# SS4.net
KiCad netlist of a schematic drawn in EAGLE
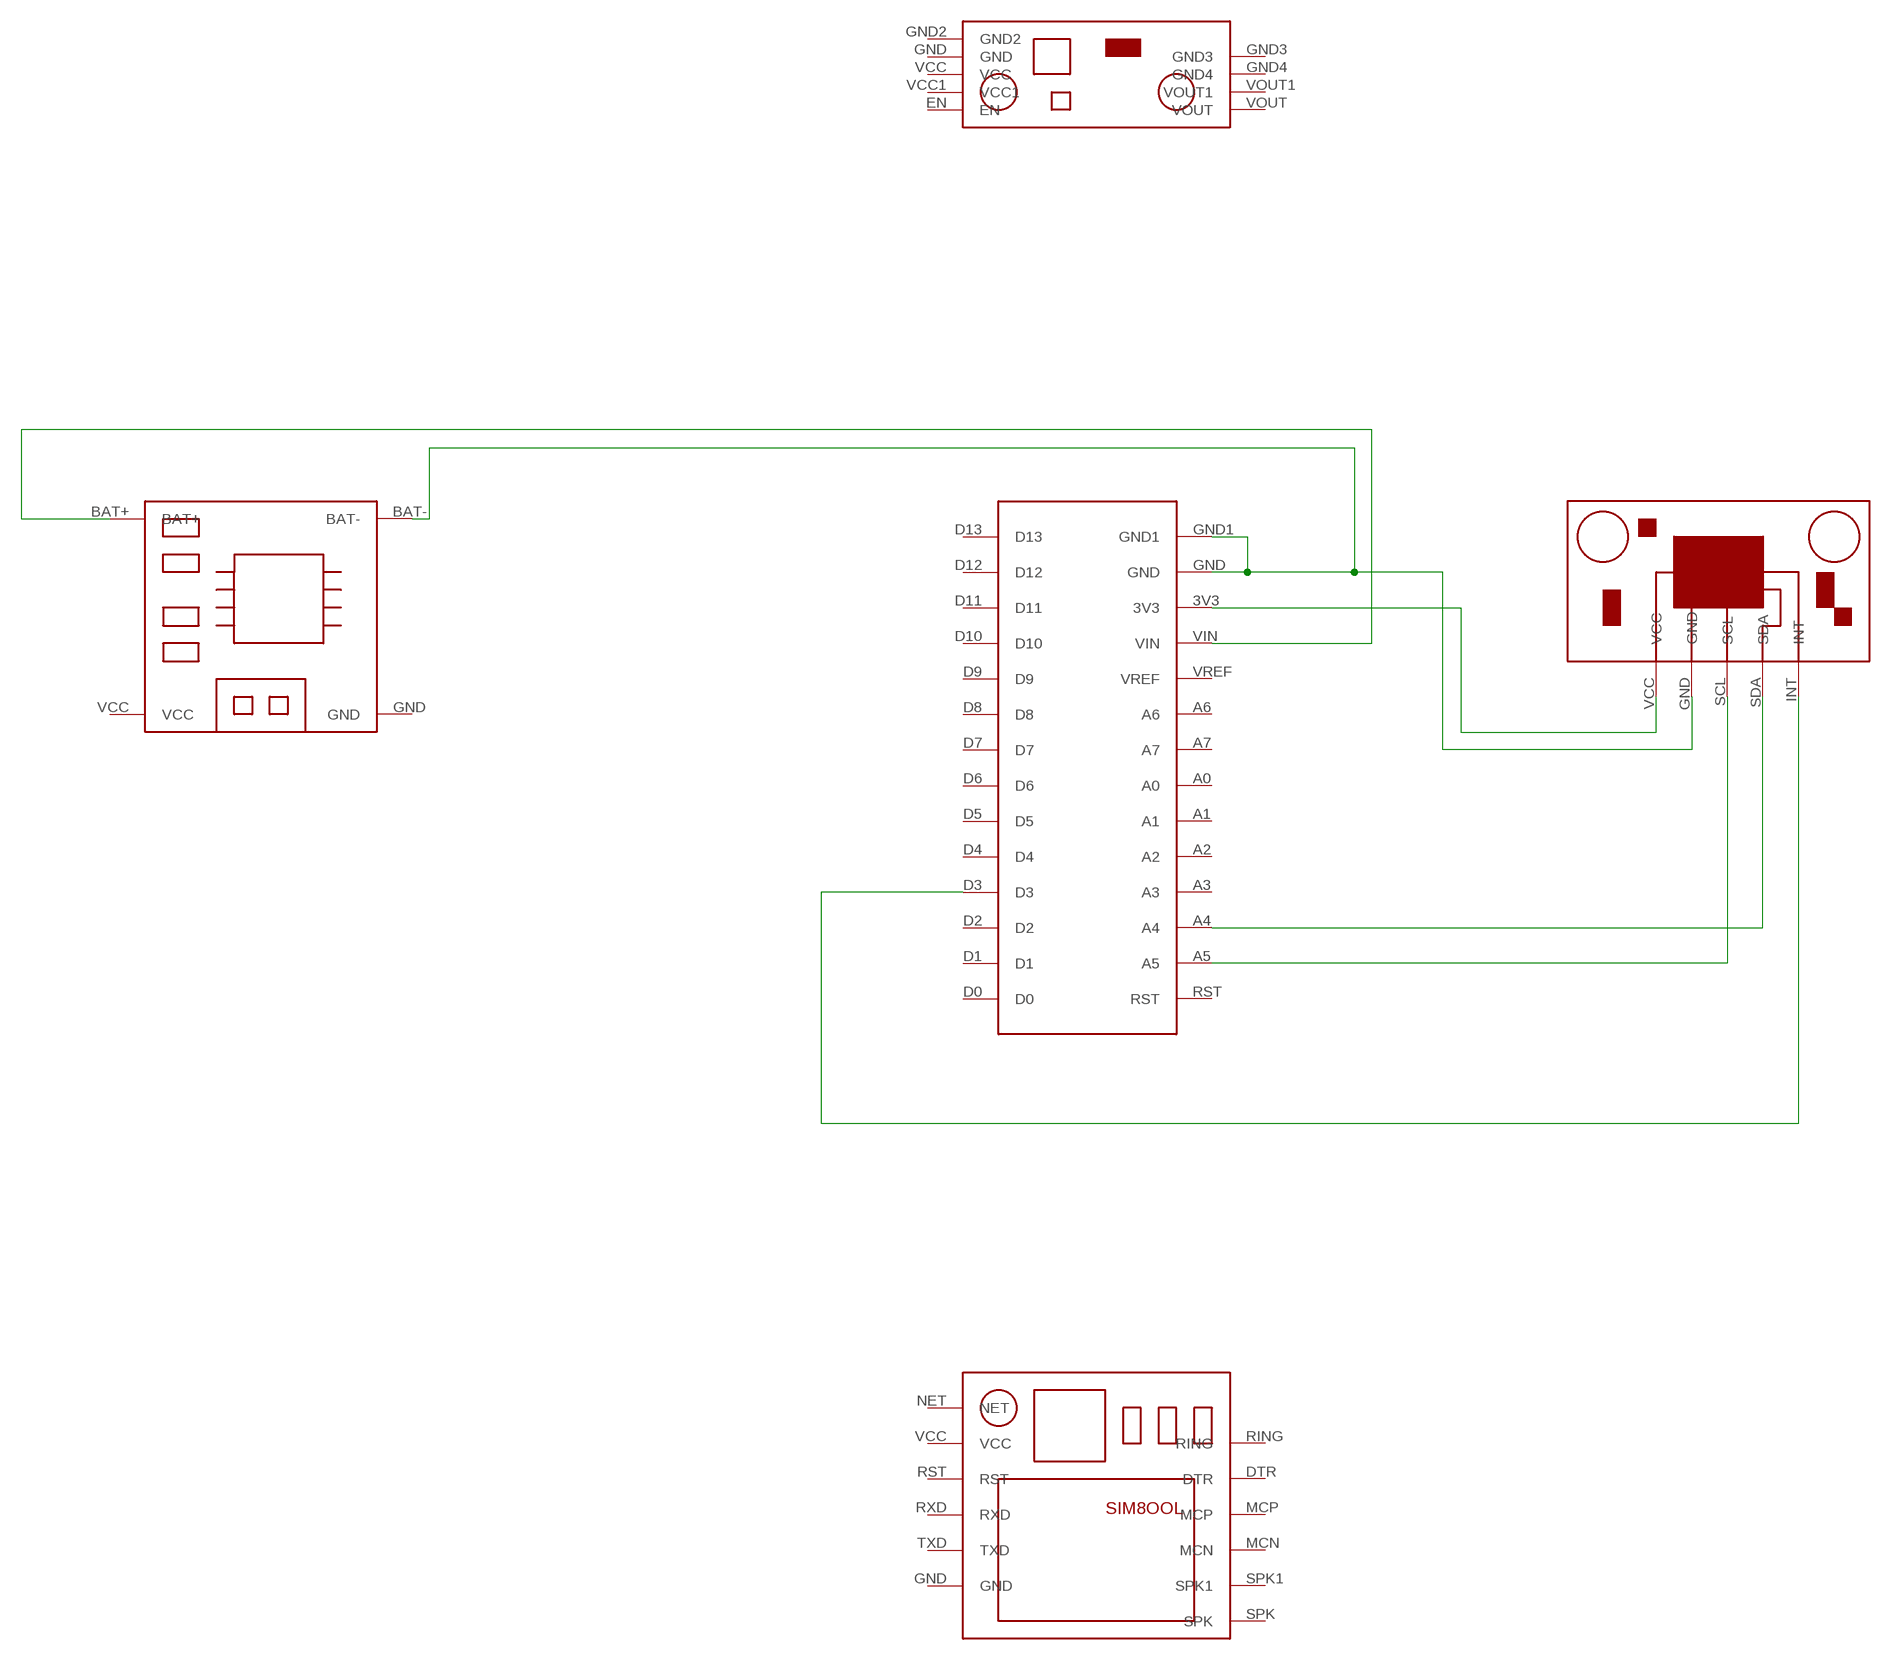
[diagram p0: schematic, sheet 1]

(export (version "E")
  (design (tool "Eeschema 10.0.6"))
  (components
    (comp (ref "U$1")
      (value "ACELEROMETER")
      (footprint "eagle-import:ACELEROMETER")
      (libsource (lib "eagle-import") (part "ACELEROMETER"))
    )
    (comp (ref "U$2")
      (value "POLOLU_STEP_UP_DOWN")
      (footprint "eagle-import:POLOLU_STEP_UP_DOWN")
      (libsource (lib "eagle-import") (part "POLOLU_STEP_UP_DOWN"))
    )
    (comp (ref "U$3")
      (value "CHARGER")
      (footprint "eagle-import:CHARGER")
      (libsource (lib "eagle-import") (part "CHARGER"))
    )
    (comp (ref "U$4")
      (value "SIM8OOL")
      (footprint "eagle-import:SIM8OOL")
      (libsource (lib "eagle-import") (part "SIM8OOL"))
    )
    (comp (ref "U$5")
      (value "ULTRA_MINI")
      (footprint "eagle-import:ULTRA_MINI")
      (libsource (lib "eagle-import") (part "ULTRA_MINI"))
    )
  )
  (nets
    (net (code "1") (name "Net-(U$1-PadGND)") (class "Default")
      (node (ref "U$1") (pin "GND") (pinfunction "GND_GND") (pintype "bidirectional"))
      (node (ref "U$3") (pin "BAT-") (pinfunction "BAT-_BAT-") (pintype "bidirectional"))
      (node (ref "U$5") (pin "GND") (pinfunction "GND_GND") (pintype "bidirectional"))
      (node (ref "U$5") (pin "GND1") (pinfunction "GND1_GND1") (pintype "bidirectional"))
    )
    (net (code "2") (name "Net-(U$1-PadINT)") (class "Default")
      (node (ref "U$1") (pin "INT") (pinfunction "INT_INT") (pintype "bidirectional"))
      (node (ref "U$5") (pin "D3") (pinfunction "D3_D3") (pintype "bidirectional"))
    )
    (net (code "3") (name "Net-(U$1-PadSCL)") (class "Default")
      (node (ref "U$1") (pin "SCL") (pinfunction "SCL_SCL") (pintype "bidirectional"))
      (node (ref "U$5") (pin "A5") (pinfunction "A5_A5") (pintype "bidirectional"))
    )
    (net (code "4") (name "Net-(U$1-PadSDA)") (class "Default")
      (node (ref "U$1") (pin "SDA") (pinfunction "SDA_SDA") (pintype "bidirectional"))
      (node (ref "U$5") (pin "A4") (pinfunction "A4_A4") (pintype "bidirectional"))
    )
    (net (code "5") (name "Net-(U$1-PadVCC)") (class "Default")
      (node (ref "U$1") (pin "VCC") (pinfunction "VCC_VCC") (pintype "bidirectional"))
      (node (ref "U$5") (pin "3V3") (pinfunction "3V3_3V3") (pintype "bidirectional"))
    )
    (net (code "6") (name "Net-(U$3-PadBAT+)") (class "Default")
      (node (ref "U$3") (pin "BAT+") (pinfunction "BAT+_BAT+") (pintype "bidirectional"))
      (node (ref "U$5") (pin "VIN") (pinfunction "VIN_VIN") (pintype "bidirectional"))
    )
    (net (code "7") (name "unconnected-(U$2-PadEN)") (class "Default")
      (node (ref "U$2") (pin "EN") (pinfunction "EN_EN") (pintype "bidirectional"))
    )
    (net (code "8") (name "unconnected-(U$2-PadGND)") (class "Default")
      (node (ref "U$2") (pin "GND") (pinfunction "GND_GND") (pintype "bidirectional"))
    )
    (net (code "9") (name "unconnected-(U$2-PadGND2)") (class "Default")
      (node (ref "U$2") (pin "GND2") (pinfunction "GND2_GND2") (pintype "bidirectional"))
    )
    (net (code "10") (name "unconnected-(U$2-PadGND3)") (class "Default")
      (node (ref "U$2") (pin "GND3") (pinfunction "GND3_GND3") (pintype "bidirectional"))
    )
    (net (code "11") (name "unconnected-(U$2-PadGND4)") (class "Default")
      (node (ref "U$2") (pin "GND4") (pinfunction "GND4_GND4") (pintype "bidirectional"))
    )
    (net (code "12") (name "unconnected-(U$2-PadVCC)") (class "Default")
      (node (ref "U$2") (pin "VCC") (pinfunction "VCC_VCC") (pintype "bidirectional"))
    )
    (net (code "13") (name "unconnected-(U$2-PadVCC1)") (class "Default")
      (node (ref "U$2") (pin "VCC1") (pinfunction "VCC1_VCC1") (pintype "bidirectional"))
    )
    (net (code "14") (name "unconnected-(U$2-PadVOUT)") (class "Default")
      (node (ref "U$2") (pin "VOUT") (pinfunction "VOUT_VOUT") (pintype "bidirectional"))
    )
    (net (code "15") (name "unconnected-(U$2-PadVOUT1)") (class "Default")
      (node (ref "U$2") (pin "VOUT1") (pinfunction "VOUT1_VOUT1") (pintype "bidirectional"))
    )
    (net (code "16") (name "unconnected-(U$3-PadGND)") (class "Default")
      (node (ref "U$3") (pin "GND") (pinfunction "GND_GND") (pintype "bidirectional"))
    )
    (net (code "17") (name "unconnected-(U$3-PadVCC)") (class "Default")
      (node (ref "U$3") (pin "VCC") (pinfunction "VCC_VCC") (pintype "bidirectional"))
    )
    (net (code "18") (name "unconnected-(U$4-PadDTR)") (class "Default")
      (node (ref "U$4") (pin "DTR") (pinfunction "DTR_DTR") (pintype "bidirectional"))
    )
    (net (code "19") (name "unconnected-(U$4-PadGND)") (class "Default")
      (node (ref "U$4") (pin "GND") (pinfunction "GND_GND") (pintype "bidirectional"))
    )
    (net (code "20") (name "unconnected-(U$4-PadMCN)") (class "Default")
      (node (ref "U$4") (pin "MCN") (pinfunction "MCN_MCN") (pintype "bidirectional"))
    )
    (net (code "21") (name "unconnected-(U$4-PadMCP)") (class "Default")
      (node (ref "U$4") (pin "MCP") (pinfunction "MCP_MCP") (pintype "bidirectional"))
    )
    (net (code "22") (name "unconnected-(U$4-PadNET)") (class "Default")
      (node (ref "U$4") (pin "NET") (pinfunction "NET_NET") (pintype "bidirectional"))
    )
    (net (code "23") (name "unconnected-(U$4-PadRING)") (class "Default")
      (node (ref "U$4") (pin "RING") (pinfunction "RING_RING") (pintype "bidirectional"))
    )
    (net (code "24") (name "unconnected-(U$4-PadRST)") (class "Default")
      (node (ref "U$4") (pin "RST") (pinfunction "RST_RST") (pintype "bidirectional"))
    )
    (net (code "25") (name "unconnected-(U$4-PadRXD)") (class "Default")
      (node (ref "U$4") (pin "RXD") (pinfunction "RXD_RXD") (pintype "bidirectional"))
    )
    (net (code "26") (name "unconnected-(U$4-PadSPK)") (class "Default")
      (node (ref "U$4") (pin "SPK") (pinfunction "SPK_SPK") (pintype "bidirectional"))
    )
    (net (code "27") (name "unconnected-(U$4-PadSPK1)") (class "Default")
      (node (ref "U$4") (pin "SPK1") (pinfunction "SPK1_SPK1") (pintype "bidirectional"))
    )
    (net (code "28") (name "unconnected-(U$4-PadTXD)") (class "Default")
      (node (ref "U$4") (pin "TXD") (pinfunction "TXD_TXD") (pintype "bidirectional"))
    )
    (net (code "29") (name "unconnected-(U$4-PadVCC)") (class "Default")
      (node (ref "U$4") (pin "VCC") (pinfunction "VCC_VCC") (pintype "bidirectional"))
    )
    (net (code "30") (name "unconnected-(U$5-PadA0)") (class "Default")
      (node (ref "U$5") (pin "A0") (pinfunction "A0_A0") (pintype "bidirectional"))
    )
    (net (code "31") (name "unconnected-(U$5-PadA1)") (class "Default")
      (node (ref "U$5") (pin "A1") (pinfunction "A1_A1") (pintype "bidirectional"))
    )
    (net (code "32") (name "unconnected-(U$5-PadA2)") (class "Default")
      (node (ref "U$5") (pin "A2") (pinfunction "A2_A2") (pintype "bidirectional"))
    )
    (net (code "33") (name "unconnected-(U$5-PadA3)") (class "Default")
      (node (ref "U$5") (pin "A3") (pinfunction "A3_A3") (pintype "bidirectional"))
    )
    (net (code "34") (name "unconnected-(U$5-PadA6)") (class "Default")
      (node (ref "U$5") (pin "A6") (pinfunction "A6_A6") (pintype "bidirectional"))
    )
    (net (code "35") (name "unconnected-(U$5-PadA7)") (class "Default")
      (node (ref "U$5") (pin "A7") (pinfunction "A7_A7") (pintype "bidirectional"))
    )
    (net (code "36") (name "unconnected-(U$5-PadD0)") (class "Default")
      (node (ref "U$5") (pin "D0") (pinfunction "D0_D0") (pintype "bidirectional"))
    )
    (net (code "37") (name "unconnected-(U$5-PadD1)") (class "Default")
      (node (ref "U$5") (pin "D1") (pinfunction "D1_D1") (pintype "bidirectional"))
    )
    (net (code "38") (name "unconnected-(U$5-PadD2)") (class "Default")
      (node (ref "U$5") (pin "D2") (pinfunction "D2_D2") (pintype "bidirectional"))
    )
    (net (code "39") (name "unconnected-(U$5-PadD4)") (class "Default")
      (node (ref "U$5") (pin "D4") (pinfunction "D4_D4") (pintype "bidirectional"))
    )
    (net (code "40") (name "unconnected-(U$5-PadD5)") (class "Default")
      (node (ref "U$5") (pin "D5") (pinfunction "D5_D5") (pintype "bidirectional"))
    )
    (net (code "41") (name "unconnected-(U$5-PadD6)") (class "Default")
      (node (ref "U$5") (pin "D6") (pinfunction "D6_D6") (pintype "bidirectional"))
    )
    (net (code "42") (name "unconnected-(U$5-PadD7)") (class "Default")
      (node (ref "U$5") (pin "D7") (pinfunction "D7_D7") (pintype "bidirectional"))
    )
    (net (code "43") (name "unconnected-(U$5-PadD8)") (class "Default")
      (node (ref "U$5") (pin "D8") (pinfunction "D8_D8") (pintype "bidirectional"))
    )
    (net (code "44") (name "unconnected-(U$5-PadD9)") (class "Default")
      (node (ref "U$5") (pin "D9") (pinfunction "D9_D9") (pintype "bidirectional"))
    )
    (net (code "45") (name "unconnected-(U$5-PadD10)") (class "Default")
      (node (ref "U$5") (pin "D10") (pinfunction "D10_D10") (pintype "bidirectional"))
    )
    (net (code "46") (name "unconnected-(U$5-PadD11)") (class "Default")
      (node (ref "U$5") (pin "D11") (pinfunction "D11_D11") (pintype "bidirectional"))
    )
    (net (code "47") (name "unconnected-(U$5-PadD12)") (class "Default")
      (node (ref "U$5") (pin "D12") (pinfunction "D12_D12") (pintype "bidirectional"))
    )
    (net (code "48") (name "unconnected-(U$5-PadD13)") (class "Default")
      (node (ref "U$5") (pin "D13") (pinfunction "D13_D13") (pintype "bidirectional"))
    )
    (net (code "49") (name "unconnected-(U$5-PadRST)") (class "Default")
      (node (ref "U$5") (pin "RST") (pinfunction "RST_RST") (pintype "bidirectional"))
    )
    (net (code "50") (name "unconnected-(U$5-PadVREF)") (class "Default")
      (node (ref "U$5") (pin "VREF") (pinfunction "VREF_VREF") (pintype "bidirectional"))
    )
  )
)
